# MotorControllerOpto-BA6229.net
KiCad netlist of a schematic drawn in EAGLE
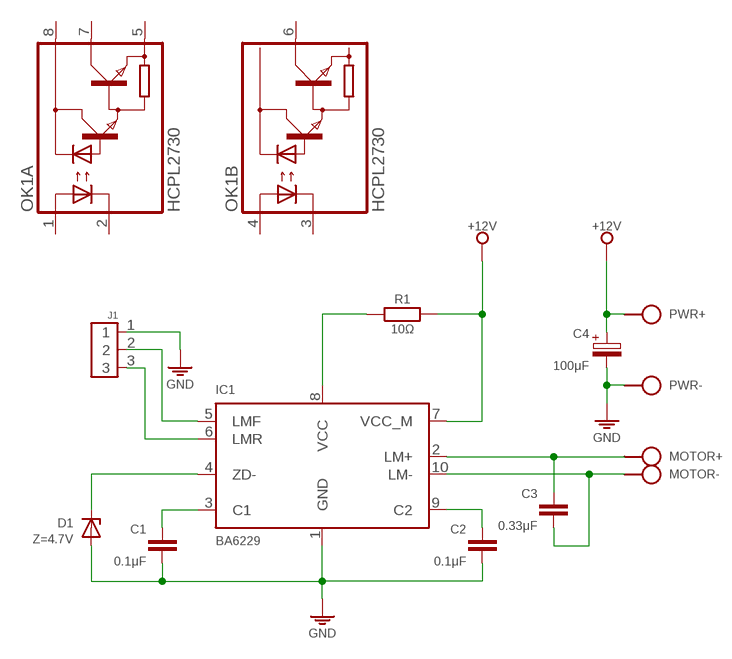
[diagram p0: schematic, sheet 1]

(export (version "E")
  (design (tool "Eeschema 10.0.6"))
  (components
    (comp (ref "C1")
      (value "0.1μF")
      (footprint "eagle-import:C050-020X044")
      (libsource (lib "eagle-import") (part "C050-020X044"))
    )
    (comp (ref "C2")
      (value "0.1μF")
      (footprint "eagle-import:C050-020X044")
      (libsource (lib "eagle-import") (part "C050-020X044"))
    )
    (comp (ref "C3")
      (value "0.33μF")
      (footprint "eagle-import:C050-020X044")
      (libsource (lib "eagle-import") (part "C050-020X044"))
    )
    (comp (ref "C4")
      (value "100μF")
      (footprint "eagle-import:E2,5-4")
      (libsource (lib "eagle-import") (part "CPOLE2,5-4"))
    )
    (comp (ref "D1")
      (value "Z=4.7V")
      (footprint "eagle-import:DO34Z5V")
      (libsource (lib "eagle-import") (part "Z-DIODE34Z5V"))
    )
    (comp (ref "IC1")
      (value "BA6229")
      (footprint "eagle-import:SIL10")
      (libsource (lib "eagle-import") (part "BA6229"))
    )
    (comp (ref "J1")
      (value "CONN-3P-3P")
      (footprint "eagle-import:CONN-3P")
      (libsource (lib "eagle-import") (part "CONN-3P-3P"))
    )
    (comp (ref "MOTOR")
      (value "SPAD+-")
      (footprint "eagle-import:SPAD+-")
      (libsource (lib "eagle-import") (part "SPAD+-"))
    )
    (comp (ref "OK1")
      (value "HCPL2730")
      (footprint "eagle-import:DIL08")
      (fields (field (name "MF") "AGILENT TECHNOLOGIES") (field (name "MPN") "HCPL-2730-000E"))
      (libsource (lib "eagle-import") (part "HCPL2730"))
    )
    (comp (ref "PWR")
      (value "SPAD+-")
      (footprint "eagle-import:SPAD+-")
      (libsource (lib "eagle-import") (part "SPAD+-"))
    )
    (comp (ref "R1")
      (value "10Ω")
      (footprint "eagle-import:0204_7-V")
      (libsource (lib "eagle-import") (part "R-H0204/7-V"))
    )
  )
  (nets
    (net (code "1") (name "+12V") (class "Default")
      (node (ref "C4") (pin "+") (pinfunction "+_+") (pintype "passive"))
      (node (ref "IC1") (pin "7") (pinfunction "VCC_M_7") (pintype "bidirectional"))
      (node (ref "PWR") (pin "2") (pinfunction "P$1_2") (pintype "passive"))
      (node (ref "R1") (pin "2") (pinfunction "2_2") (pintype "passive"))
    )
    (net (code "2") (name "GND") (class "Default")
      (node (ref "C1") (pin "2") (pinfunction "2_2") (pintype "passive"))
      (node (ref "C2") (pin "2") (pinfunction "2_2") (pintype "passive"))
      (node (ref "C4") (pin "-") (pinfunction "-_-") (pintype "passive"))
      (node (ref "D1") (pin "A") (pinfunction "A_A") (pintype "passive"))
      (node (ref "IC1") (pin "1") (pinfunction "GND_1") (pintype "bidirectional"))
      (node (ref "J1") (pin "1") (pinfunction "1_1") (pintype "bidirectional"))
      (node (ref "PWR") (pin "1") (pinfunction "P$1_1") (pintype "passive"))
    )
    (net (code "3") (name "Net-(IC1-C1)") (class "Default")
      (node (ref "C1") (pin "1") (pinfunction "1_1") (pintype "passive"))
      (node (ref "IC1") (pin "3") (pinfunction "C1_3") (pintype "bidirectional"))
    )
    (net (code "4") (name "Net-(IC1-C2)") (class "Default")
      (node (ref "C2") (pin "1") (pinfunction "1_1") (pintype "passive"))
      (node (ref "IC1") (pin "9") (pinfunction "C2_9") (pintype "bidirectional"))
    )
    (net (code "5") (name "Net-(IC1-LM+)") (class "Default")
      (node (ref "C3") (pin "1") (pinfunction "1_1") (pintype "passive"))
      (node (ref "IC1") (pin "2") (pinfunction "LM+_2") (pintype "bidirectional"))
      (node (ref "MOTOR") (pin "2") (pinfunction "P$1_2") (pintype "passive"))
    )
    (net (code "6") (name "Net-(IC1-LM-)") (class "Default")
      (node (ref "C3") (pin "2") (pinfunction "2_2") (pintype "passive"))
      (node (ref "IC1") (pin "10") (pinfunction "LM-_10") (pintype "bidirectional"))
      (node (ref "MOTOR") (pin "1") (pinfunction "P$1_1") (pintype "passive"))
    )
    (net (code "7") (name "Net-(IC1-LMF)") (class "Default")
      (node (ref "IC1") (pin "5") (pinfunction "LMF_5") (pintype "bidirectional"))
      (node (ref "J1") (pin "2") (pinfunction "2_2") (pintype "bidirectional"))
    )
    (net (code "8") (name "Net-(IC1-LMR)") (class "Default")
      (node (ref "IC1") (pin "6") (pinfunction "LMR_6") (pintype "bidirectional"))
      (node (ref "J1") (pin "3") (pinfunction "3_3") (pintype "bidirectional"))
    )
    (net (code "9") (name "Net-(IC1-VCC)") (class "Default")
      (node (ref "IC1") (pin "8") (pinfunction "VCC_8") (pintype "bidirectional"))
      (node (ref "R1") (pin "1") (pinfunction "1_1") (pintype "passive"))
    )
    (net (code "10") (name "Net-(IC1-ZD-)") (class "Default")
      (node (ref "D1") (pin "C") (pinfunction "C_C") (pintype "passive"))
      (node (ref "IC1") (pin "4") (pinfunction "ZD-_4") (pintype "bidirectional"))
    )
    (net (code "11") (name "unconnected-(OK1A-A1-Pad1)") (class "Default")
      (node (ref "OK1") (pin "1") (pinfunction "A1_1") (pintype "passive"))
    )
    (net (code "12") (name "unconnected-(OK1A-C1-Pad2)") (class "Default")
      (node (ref "OK1") (pin "2") (pinfunction "C1_2") (pintype "passive"))
    )
    (net (code "13") (name "unconnected-(OK1A-GND-Pad5)") (class "Default")
      (node (ref "OK1") (pin "5") (pinfunction "GND_5") (pintype "passive"))
    )
    (net (code "14") (name "unconnected-(OK1A-VCC-Pad8)") (class "Default")
      (node (ref "OK1") (pin "8") (pinfunction "VCC_8") (pintype "passive"))
    )
    (net (code "15") (name "unconnected-(OK1A-VO1-Pad7)") (class "Default")
      (node (ref "OK1") (pin "7") (pinfunction "VO1_7") (pintype "passive"))
    )
    (net (code "16") (name "unconnected-(OK1B-A2-Pad4)") (class "Default")
      (node (ref "OK1") (pin "4") (pinfunction "A2_4") (pintype "passive"))
    )
    (net (code "17") (name "unconnected-(OK1B-C2-Pad3)") (class "Default")
      (node (ref "OK1") (pin "3") (pinfunction "C2_3") (pintype "passive"))
    )
    (net (code "18") (name "unconnected-(OK1B-VO2-Pad6)") (class "Default")
      (node (ref "OK1") (pin "6") (pinfunction "VO2_6") (pintype "passive"))
    )
  )
)
